# Power.net
KiCad netlist of a schematic drawn in Altium Designer
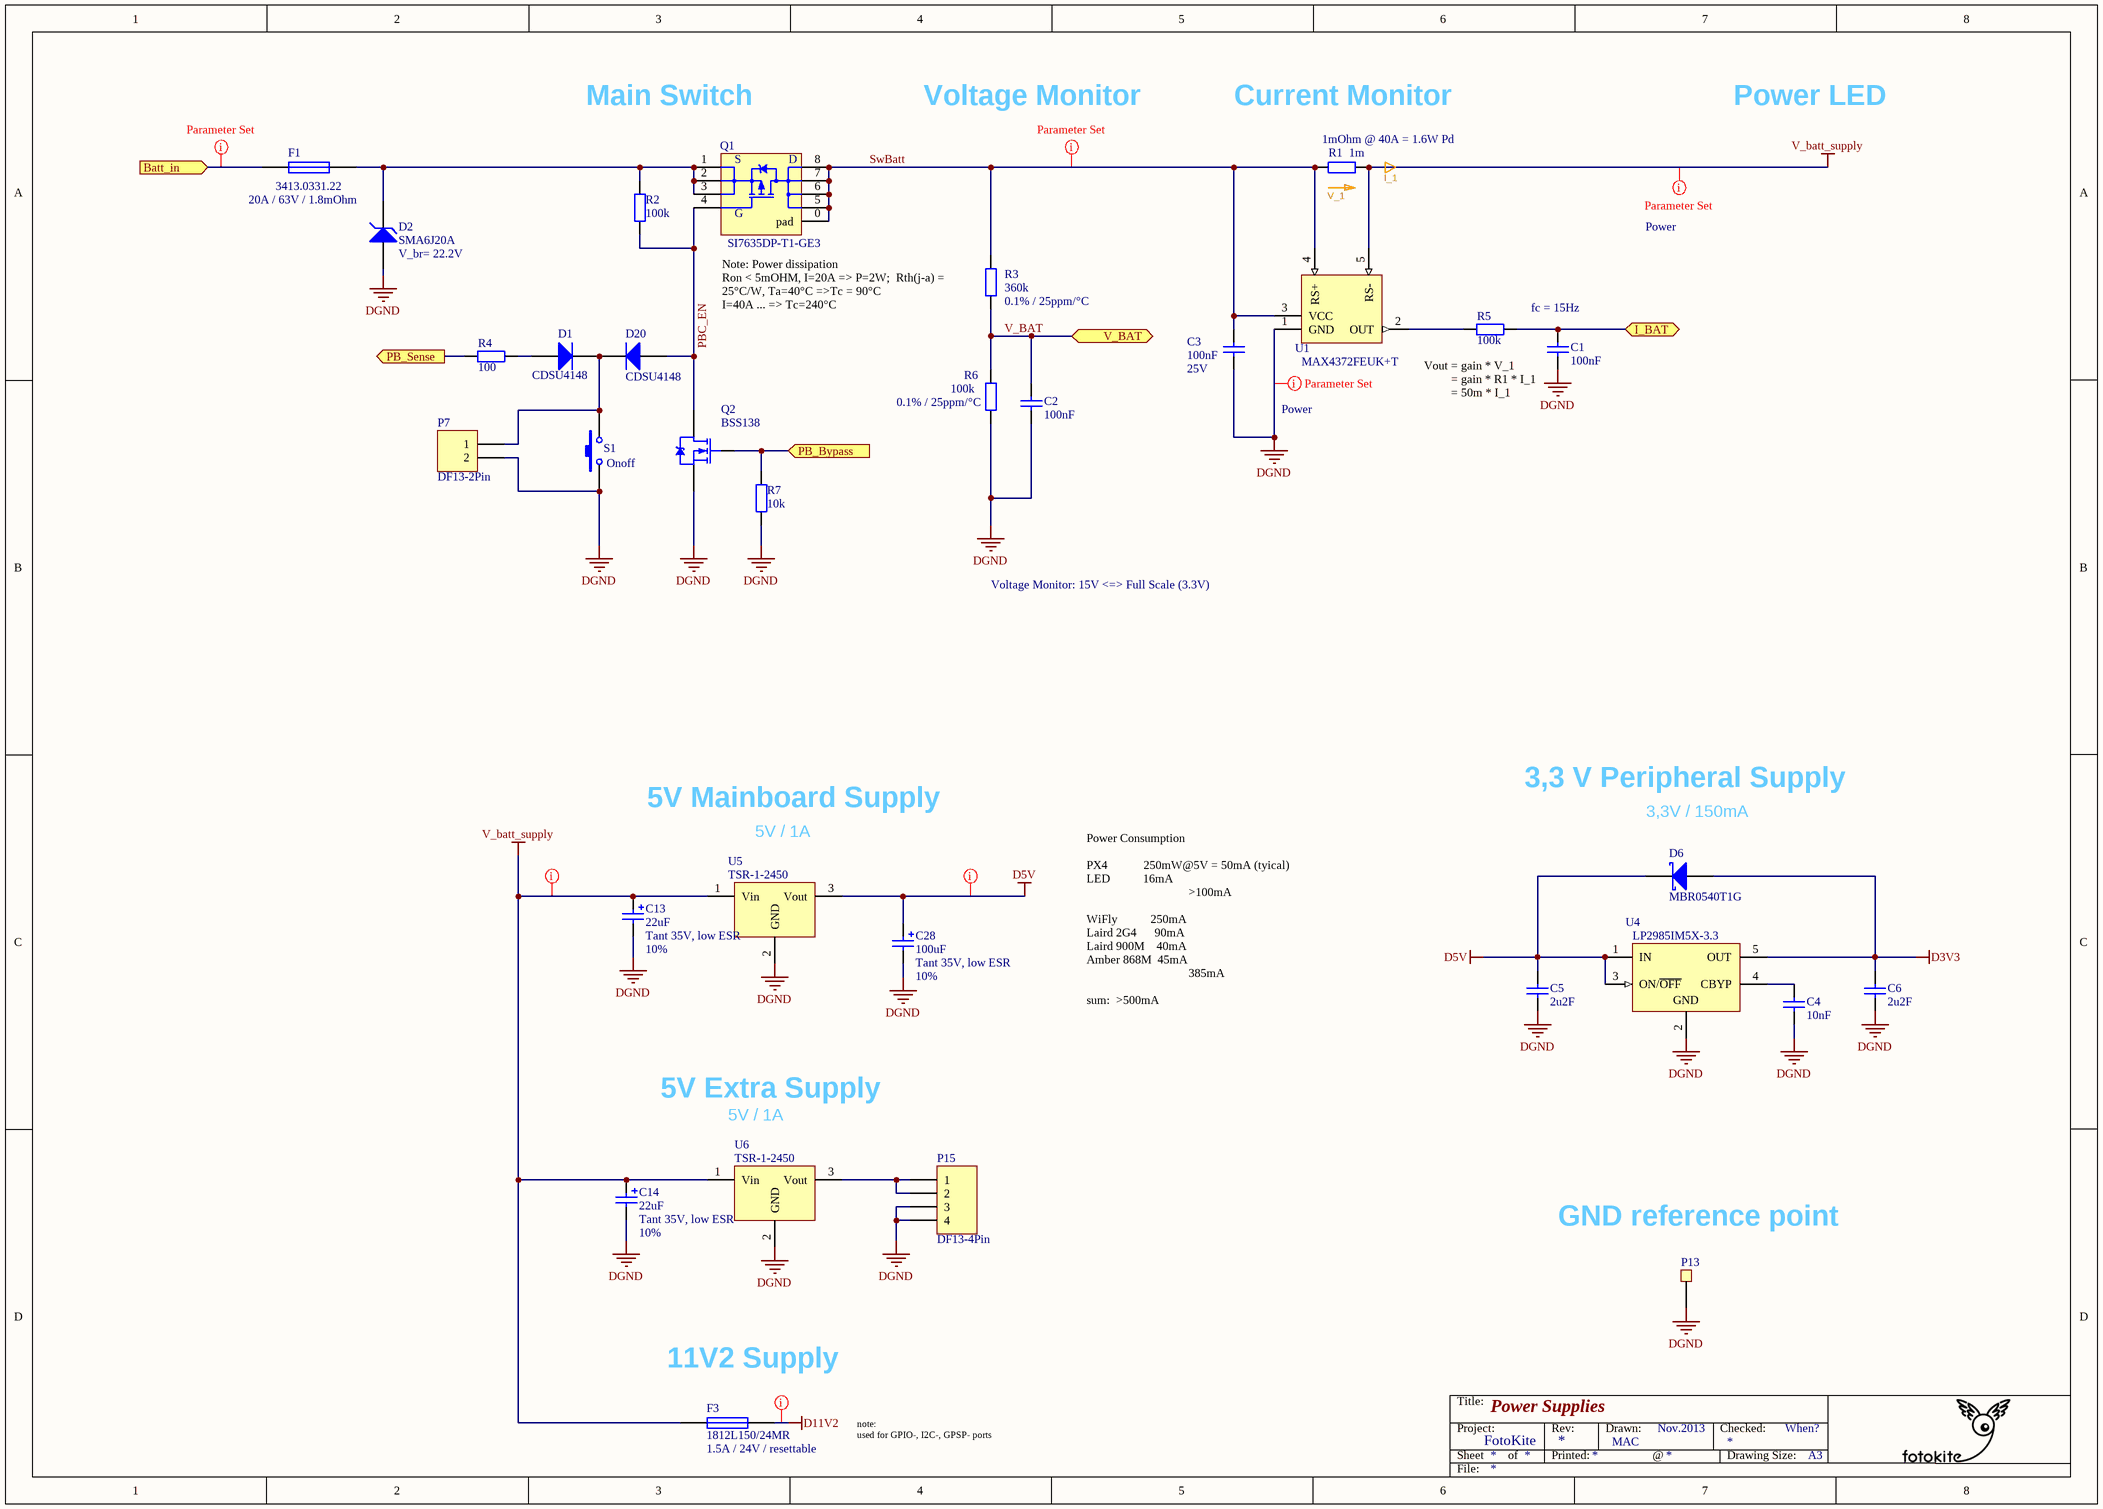
[diagram p0: Power.SchDoc]

(export (version "E")
  (design (tool "Eeschema 10.0.6"))
  (components
    (comp (ref "C1")
      (value "100nF")
      (footprint "CAP_0603i_1608m -N")
      (description "capacitor")
      (libsource (lib "IDSC std generic parts ") (part "Cap"))
    )
    (comp (ref "C2")
      (value "100nF")
      (footprint "CAP_0603i_1608m -N")
      (description "capacitor")
      (libsource (lib "IDSC std generic parts ") (part "Cap"))
    )
    (comp (ref "C3")
      (value "100nF")
      (footprint "CAP_0603i_1608m -N")
      (description "capacitor")
      (fields (field (name "NOTE") "25V"))
      (libsource (lib "IDSC std generic parts ") (part "Cap"))
    )
    (comp (ref "C4")
      (value "10nF")
      (footprint "CAP_0603i_1608m -N")
      (description "capacitor")
      (libsource (lib "IDSC std generic parts ") (part "Cap"))
    )
    (comp (ref "C5")
      (value "2u2F")
      (footprint "CAP_0603i_1608m -N")
      (description "capacitor")
      (libsource (lib "IDSC std generic parts ") (part "Cap"))
    )
    (comp (ref "C6")
      (value "2u2F")
      (footprint "CAP_0603i_1608m -N")
      (description "capacitor")
      (libsource (lib "IDSC std generic parts ") (part "Cap"))
    )
    (comp (ref "C13")
      (value "22uF")
      (footprint "EIA-7343-31 case D -N")
      (description "Polarised capacitor (e.g. Electrolytic )")
      (fields (field (name "NOTE") "Tant 35V, low ESR") (field (name "TOLERANCE") "10%"))
      (libsource (lib "IDSC std generic parts ") (part "Cap pol"))
    )
    (comp (ref "C14")
      (value "22uF")
      (footprint "EIA-7343-31 case D -N")
      (description "Polarised capacitor (e.g. Electrolytic )")
      (fields (field (name "NOTE") "Tant 35V, low ESR") (field (name "TOLERANCE") "10%"))
      (libsource (lib "IDSC std generic parts ") (part "Cap pol"))
    )
    (comp (ref "C28")
      (value "100uF")
      (footprint "EIA-7343-31 case D -N")
      (description "Polarised capacitor (e.g. Electrolytic )")
      (fields (field (name "NOTE") "Tant 35V, low ESR") (field (name "TOLERANCE") "10%"))
      (libsource (lib "IDSC std generic parts ") (part "Cap pol"))
    )
    (comp (ref "D1")
      (value "CDSU4148")
      (footprint "SOD523F")
      (description "Default Diode")
      (libsource (lib "IDSC std generic parts ") (part "Diode"))
    )
    (comp (ref "D2")
      (value "SMA6J20A")
      (footprint "Mini MELF - SOD-80 -N")
      (description "Zener Diode")
      (fields (field (name "NOTE") "V_br= 22.2V"))
      (libsource (lib "IDSC std generic parts ") (part "Diode Zener"))
    )
    (comp (ref "D6")
      (value "MBR0540T1G")
      (footprint "SOD123")
      (description "Schottky Diode")
      (libsource (lib "IDSC std generic parts ") (part "Diode  Schottky"))
    )
    (comp (ref "D20")
      (value "CDSU4148")
      (footprint "SOD523F")
      (description "Default Diode")
      (libsource (lib "IDSC std generic parts ") (part "Diode"))
    )
    (comp (ref "F1")
      (value "3413.0331.22")
      (footprint "Fuse_1210i_3225m -N")
      (description "Fuse")
      (fields (field (name "NOTE") "20A / 63V / 1.8mOhm"))
      (libsource (lib "IDSC std generic parts ") (part "Fuse"))
    )
    (comp (ref "F3")
      (value "1812L150/24MR")
      (footprint "Fuse_1812i_4532m -N")
      (description "Fuse")
      (fields (field (name "ALTIUM_VALUE") "1.5A / 24V / resettable"))
      (libsource (lib "IDSC std generic parts ") (part "Fuse"))
    )
    (comp (ref "P7")
      (value "DF13-2Pin")
      (footprint "Hirose_DF13_SMT_RA_N2")
      (description "Hirose_DF13_SMT_RA_N2")
      (libsource (lib "IDSC std connectors") (part "DF13-2Pin"))
    )
    (comp (ref "P13")
      (value "GND")
      (footprint "PIN1")
      (description "Single Pad or Testpoint")
      (libsource (lib "IDSC std connectors") (part "Pad"))
    )
    (comp (ref "P15")
      (value "DF13-4Pin")
      (footprint "Hirose_DF13_SMT_RA_N4")
      (description "Hirose_DF13_SMT_RA_N4")
      (libsource (lib "IDSC std connectors") (part "DF13-4Pin"))
    )
    (comp (ref "Q1")
      (value "SI7635DP-T1-GE3")
      (footprint "PowerPak SO-8")
      (description "Power P-Channel MOSFET + pad")
      (libsource (lib "IDSC std generic parts ") (part "MOSFET-P-Power_2"))
    )
    (comp (ref "Q2")
      (value "BSS138")
      (footprint "SOT23-N")
      (description "N-Channel MOSFET")
      (libsource (lib "IDSC std generic parts ") (part "MOSFET-N2"))
    )
    (comp (ref "R1")
      (value "1m")
      (footprint "RES_2512i_6332m -N")
      (description "Resistor")
      (fields (field (name "TOLERANCE") "1%/50ppm/°C"))
      (libsource (lib "") (part "Res_2"))
    )
    (comp (ref "R2")
      (value "100k")
      (footprint "RES_0603i_1608m -N")
      (description "Resistor")
      (libsource (lib "IDSC std generic parts ") (part "Res"))
    )
    (comp (ref "R3")
      (value "360k")
      (footprint "RES_0603i_1608m -N")
      (description "Resistor")
      (fields (field (name "TOLERANCE") "0.1% / 25ppm/°C"))
      (libsource (lib "IDSC std generic parts ") (part "Res"))
    )
    (comp (ref "R4")
      (value "100")
      (footprint "RES_0603i_1608m -N")
      (description "Resistor")
      (libsource (lib "") (part "Res_1"))
    )
    (comp (ref "R5")
      (value "100k")
      (footprint "RES_0603i_1608m -N")
      (description "Resistor")
      (libsource (lib "") (part "Res_2"))
    )
    (comp (ref "R6")
      (value "100k")
      (footprint "RES_0603i_1608m -N")
      (description "Resistor")
      (fields (field (name "TOLERANCE") "0.1% / 25ppm/°C"))
      (libsource (lib "IDSC std generic parts ") (part "Res"))
    )
    (comp (ref "R7")
      (value "10k")
      (footprint "RES_0603i_1608m -N")
      (description "Resistor")
      (libsource (lib "IDSC std generic parts ") (part "Res"))
    )
    (comp (ref "S1")
      (value "EVQ-PUB02K")
      (footprint "EVQPU")
      (description "Switch")
      (fields (field (name "NOTE") "Onoff"))
      (libsource (lib "IDSC std generic parts ") (part "SW PB"))
    )
    (comp (ref "U1")
      (value "MAX4372FEUK+T")
      (footprint "MAXM-U5+1_N")
      (libsource (lib "Altium Content Vault") (part "CMP-0252-00304-1"))
    )
    (comp (ref "U4")
      (value "LP2985IM5X-3.3")
      (footprint "MF05A_N")
      (description "Micropower 150 mA Low-Noise Ultra Low-Dropout Regulator, 5-pin SOT-23")
      (fields (field (name "MANUFACTURER") "National Semiconductor"))
      (libsource (lib "Altium Content Vault") (part "CMP-0062-01952-2"))
    )
    (comp (ref "U5")
      (value "TSR-1-2450")
      (footprint "TST-1")
      (description "DC/DC Converter; different Voltages; 1A; Traco")
      (libsource (lib "IDSC_component_lib") (part "TSR-1-24xx"))
    )
    (comp (ref "U6")
      (value "TSR-1-2450")
      (footprint "TST-1")
      (description "DC/DC Converter; different Voltages; 1A; Traco")
      (libsource (lib "IDSC_component_lib") (part "TSR-1-24xx"))
    )
  )
  (nets
    (net (code "1") (name "/Batt_in") (class "Default")
      (node (ref "F1") (pin "1") (pinfunction "1_1") (pintype "passive"))
    )
    (net (code "2") (name "/I_BAT") (class "Default")
      (node (ref "C1") (pin "2") (pinfunction "2_2") (pintype "passive"))
      (node (ref "R5") (pin "2") (pinfunction "2_2") (pintype "passive"))
    )
    (net (code "3") (name "/PBC_EN") (class "Default")
      (node (ref "D20") (pin "1") (pinfunction "A_1") (pintype "passive"))
      (node (ref "Q1") (pin "4") (pinfunction "G_4") (pintype "passive"))
      (node (ref "Q2") (pin "3") (pinfunction "D_3") (pintype "passive"))
      (node (ref "R2") (pin "1") (pinfunction "1_1") (pintype "passive"))
    )
    (net (code "4") (name "/PB_Bypass") (class "Default")
      (node (ref "Q2") (pin "1") (pinfunction "G_1") (pintype "passive"))
      (node (ref "R7") (pin "2") (pinfunction "2_2") (pintype "passive"))
    )
    (net (code "5") (name "/PB_Sense") (class "Default")
      (node (ref "R4") (pin "2") (pinfunction "2_2") (pintype "passive"))
    )
    (net (code "6") (name "/SwBatt") (class "Default")
      (node (ref "C3") (pin "2") (pinfunction "2_2") (pintype "passive"))
      (node (ref "Q1") (pin "0") (pinfunction "pad_0") (pintype "passive"))
      (node (ref "Q1") (pin "5") (pinfunction "D_5") (pintype "passive"))
      (node (ref "Q1") (pin "6") (pinfunction "D_6") (pintype "passive"))
      (node (ref "Q1") (pin "7") (pinfunction "D_7") (pintype "passive"))
      (node (ref "Q1") (pin "8") (pinfunction "D_8") (pintype "passive"))
      (node (ref "R1") (pin "1") (pinfunction "1_1") (pintype "passive"))
      (node (ref "R3") (pin "2") (pinfunction "2_2") (pintype "passive"))
      (node (ref "U1") (pin "3") (pinfunction "VCC_3") (pintype "power_in"))
      (node (ref "U1") (pin "4") (pinfunction "RS+_4") (pintype "input"))
    )
    (net (code "7") (name "/V_BAT") (class "Default")
      (node (ref "C2") (pin "2") (pinfunction "2_2") (pintype "passive"))
      (node (ref "R3") (pin "1") (pinfunction "1_1") (pintype "passive"))
      (node (ref "R6") (pin "2") (pinfunction "2_2") (pintype "passive"))
    )
    (net (code "8") (name "D3V3") (class "Default")
      (node (ref "C6") (pin "2") (pinfunction "2_2") (pintype "passive"))
      (node (ref "D6") (pin "1") (pinfunction "A_1") (pintype "passive"))
      (node (ref "U4") (pin "5") (pinfunction "OUT_5") (pintype "power_in"))
    )
    (net (code "9") (name "D5V") (class "Default")
      (node (ref "C28") (pin "1") (pinfunction "1_1") (pintype "passive"))
      (node (ref "C5") (pin "2") (pinfunction "2_2") (pintype "passive"))
      (node (ref "D6") (pin "2") (pinfunction "K_2") (pintype "passive"))
      (node (ref "U4") (pin "1") (pinfunction "IN_1") (pintype "power_in"))
      (node (ref "U4") (pin "3") (pinfunction "ON/~{OFF}_3") (pintype "input"))
      (node (ref "U5") (pin "3") (pinfunction "Vout_3") (pintype "power_in"))
    )
    (net (code "10") (name "D11V2") (class "Default")
      (node (ref "F3") (pin "2") (pinfunction "2_2") (pintype "passive"))
    )
    (net (code "11") (name "DGND") (class "Default")
      (node (ref "C1") (pin "1") (pinfunction "1_1") (pintype "passive"))
      (node (ref "C13") (pin "2") (pinfunction "2_2") (pintype "passive"))
      (node (ref "C14") (pin "2") (pinfunction "2_2") (pintype "passive"))
      (node (ref "C2") (pin "1") (pinfunction "1_1") (pintype "passive"))
      (node (ref "C28") (pin "2") (pinfunction "2_2") (pintype "passive"))
      (node (ref "C3") (pin "1") (pinfunction "1_1") (pintype "passive"))
      (node (ref "C4") (pin "1") (pinfunction "1_1") (pintype "passive"))
      (node (ref "C5") (pin "1") (pinfunction "1_1") (pintype "passive"))
      (node (ref "C6") (pin "1") (pinfunction "1_1") (pintype "passive"))
      (node (ref "D2") (pin "1") (pinfunction "A_1") (pintype "passive"))
      (node (ref "P13") (pin "1") (pinfunction "1_1") (pintype "passive"))
      (node (ref "P15") (pin "3") (pinfunction "3_3") (pintype "passive"))
      (node (ref "P15") (pin "4") (pinfunction "4_4") (pintype "passive"))
      (node (ref "P7") (pin "2") (pinfunction "2_2") (pintype "passive"))
      (node (ref "Q2") (pin "2") (pinfunction "S_2") (pintype "passive"))
      (node (ref "R6") (pin "1") (pinfunction "1_1") (pintype "passive"))
      (node (ref "R7") (pin "1") (pinfunction "1_1") (pintype "passive"))
      (node (ref "S1") (pin "2") (pinfunction "2_2") (pintype "passive"))
      (node (ref "U1") (pin "1") (pinfunction "GND_1") (pintype "power_in"))
      (node (ref "U4") (pin "2") (pinfunction "GND_2") (pintype "power_in"))
      (node (ref "U5") (pin "2") (pinfunction "GND_2") (pintype "power_in"))
      (node (ref "U6") (pin "2") (pinfunction "GND_2") (pintype "power_in"))
    )
    (net (code "12") (name "Net-(D1-A)") (class "Default")
      (node (ref "D1") (pin "1") (pinfunction "A_1") (pintype "passive"))
      (node (ref "R4") (pin "1") (pinfunction "1_1") (pintype "passive"))
    )
    (net (code "13") (name "Net-(D1-K)") (class "Default")
      (node (ref "D1") (pin "2") (pinfunction "K_2") (pintype "passive"))
      (node (ref "D20") (pin "2") (pinfunction "K_2") (pintype "passive"))
      (node (ref "P7") (pin "1") (pinfunction "1_1") (pintype "passive"))
      (node (ref "S1") (pin "1") (pinfunction "1_1") (pintype "passive"))
    )
    (net (code "14") (name "Net-(D2-K)") (class "Default")
      (node (ref "D2") (pin "2") (pinfunction "K_2") (pintype "passive"))
      (node (ref "F1") (pin "2") (pinfunction "2_2") (pintype "passive"))
      (node (ref "Q1") (pin "1") (pinfunction "S_1") (pintype "passive"))
      (node (ref "Q1") (pin "2") (pinfunction "S_2") (pintype "passive"))
      (node (ref "Q1") (pin "3") (pinfunction "S_3") (pintype "passive"))
      (node (ref "R2") (pin "2") (pinfunction "2_2") (pintype "passive"))
    )
    (net (code "15") (name "Net-(U1-OUT)") (class "Default")
      (node (ref "R5") (pin "1") (pinfunction "1_1") (pintype "passive"))
      (node (ref "U1") (pin "2") (pinfunction "OUT_2") (pintype "output"))
    )
    (net (code "16") (name "Net-(U4-CBYP)") (class "Default")
      (node (ref "C4") (pin "2") (pinfunction "2_2") (pintype "passive"))
      (node (ref "U4") (pin "4") (pinfunction "CBYP_4") (pintype "passive"))
    )
    (net (code "17") (name "Net-(U6-Vout)") (class "Default")
      (node (ref "P15") (pin "1") (pinfunction "1_1") (pintype "passive"))
      (node (ref "P15") (pin "2") (pinfunction "2_2") (pintype "passive"))
      (node (ref "U6") (pin "3") (pinfunction "Vout_3") (pintype "power_in"))
    )
    (net (code "18") (name "V_batt_supply") (class "Default")
      (node (ref "C13") (pin "1") (pinfunction "1_1") (pintype "passive"))
      (node (ref "C14") (pin "1") (pinfunction "1_1") (pintype "passive"))
      (node (ref "F3") (pin "1") (pinfunction "1_1") (pintype "passive"))
      (node (ref "R1") (pin "2") (pinfunction "2_2") (pintype "passive"))
      (node (ref "U1") (pin "5") (pinfunction "RS-_5") (pintype "input"))
      (node (ref "U5") (pin "1") (pinfunction "Vin_1") (pintype "power_in"))
      (node (ref "U6") (pin "1") (pinfunction "Vin_1") (pintype "power_in"))
    )
  )
)
